# Sheet1.net
KiCad netlist of a schematic drawn in Altium Designer
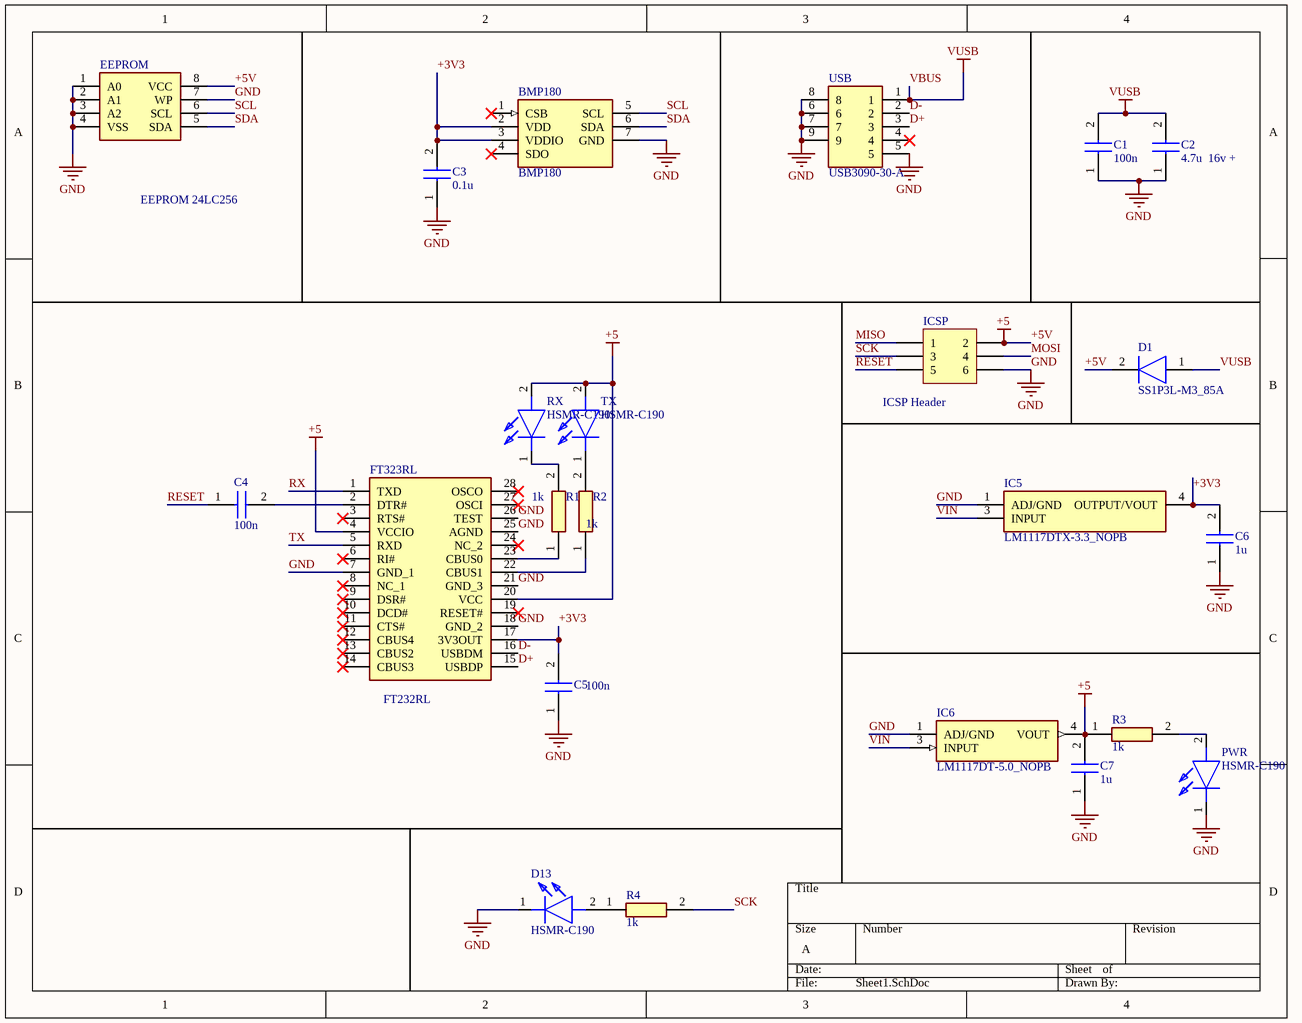
[diagram p0: Sheet1.SchDoc]

(export (version "E")
  (design (tool "Eeschema 10.0.6"))
  (components
    (comp (ref "BMP180")
      (value "BMP180")
      (footprint "SamacSys:BMP180")
      (description "Integrated Circuit")
      (fields (field (name "MOUSER PART NUMBER") "262-BMP180"))
      (libsource (lib "SamacSys") (part "BMP180"))
    )
    (comp (ref "C1")
      (value "100n")
      (footprint "SamacSys:CAPC1608X87N")
      (description "Capacitor")
      (fields (field (name "MANUFACTURER_PART_NUMBER") "C0603C569J5GACTU"))
      (libsource (lib "SamacSys") (part "C0603C569J5GACTU"))
    )
    (comp (ref "C2")
      (value "4.7u  16v +")
      (footprint "SamacSys:CAPC1608X87N")
      (description "Capacitor")
      (fields (field (name "MANUFACTURER_PART_NUMBER") "C0603C569J5GACTU"))
      (libsource (lib "SamacSys") (part "C0603C569J5GACTU"))
    )
    (comp (ref "C3")
      (value "0.1u")
      (footprint "SamacSys:CAPC1608X87N")
      (description "Capacitor")
      (fields (field (name "MANUFACTURER_PART_NUMBER") "C0603C569J5GACTU"))
      (libsource (lib "*") (part "C0603C569J5GACTU"))
    )
    (comp (ref "C4")
      (value "100n")
      (footprint "SamacSys:CAPC1608X87N")
      (description "Capacitor")
      (fields (field (name "MANUFACTURER_PART_NUMBER") "C0603C569J5GACTU"))
      (libsource (lib "*") (part "C0603C569J5GACTU"))
    )
    (comp (ref "C5")
      (value "100n")
      (footprint "SamacSys:CAPC1608X87N")
      (description "Capacitor")
      (fields (field (name "MANUFACTURER_PART_NUMBER") "C0603C569J5GACTU"))
      (libsource (lib "SamacSys") (part "C0603C569J5GACTU"))
    )
    (comp (ref "C6")
      (value "1u")
      (footprint "SamacSys:CAPC1608X87N")
      (description "Capacitor")
      (fields (field (name "MANUFACTURER_PART_NUMBER") "C0603C569J5GACTU"))
      (libsource (lib "SamacSys") (part "C0603C569J5GACTU"))
    )
    (comp (ref "C7")
      (value "1u")
      (footprint "SamacSys:CAPC1608X87N")
      (description "Capacitor")
      (fields (field (name "MANUFACTURER_PART_NUMBER") "C0603C569J5GACTU"))
      (libsource (lib "SamacSys") (part "C0603C569J5GACTU"))
    )
    (comp (ref "D1")
      (value "SS1P3L-M3_85A")
      (footprint "SamacSys:SMP")
      (description "Diode")
      (fields
        (field (name "MANUFACTURER_PART_NUMBER") "SS1P3L-M3/85A")
        (field (name "MOUSER PART NUMBER") "625-SS1P3L-M3/85A")
      )
      (libsource (lib "SamacSys") (part "SS1P3L-M3_85A"))
    )
    (comp (ref "D13")
      (value "HSMR-C190")
      (footprint "SamacSys:LEDC1608X80N")
      (description "LED")
      (fields (field (name "MOUSER PART NUMBER") "630-HSMR-C190"))
      (libsource (lib "SamacSys") (part "HSMR-C190"))
    )
    (comp (ref "EEPROM")
      (value "EEPROM 24LC256")
      (footprint "SamacSys:SOP65P490X110-8N")
      (description "Integrated Circuit")
      (fields
        (field (name "MANUFACTURER_PART_NUMBER") "24LC256-I/MS")
        (field (name "MOUSER PART NUMBER") "579-24LC256-I/MS")
      )
      (libsource (lib "*") (part "24LC256-I_MS"))
    )
    (comp (ref "FT323RL")
      (value "FT232RL")
      (footprint "SamacSys:SOP65P778X200-28N")
      (description "Integrated Circuit")
      (fields
        (field (name "MANUFACTURER_PART_NUMBER") "FT232RL-REEL")
        (field (name "MOUSER PART NUMBER") "895-FT232RL")
      )
      (libsource (lib "*") (part "FT232RL-REEL"))
    )
    (comp (ref "IC5")
      (value "LM1117DTX-3.3_NOPB")
      (footprint "SamacSys:LM1117DTX33NOPB")
      (description "Integrated Circuit")
      (fields
        (field (name "MANUFACTURER_PART_NUMBER") "LM1117DTX-3.3/NOPB")
        (field (name "MOUSER PART NUMBER") "926-LM1117DTX3.3NOPB")
      )
      (libsource (lib "SamacSys") (part "LM1117DTX-3.3_NOPB"))
    )
    (comp (ref "IC6")
      (value "LM1117DT-5.0_NOPB")
      (footprint "SamacSys:TO228P991X238-3N")
      (description "Integrated Circuit")
      (fields
        (field (name "MANUFACTURER_PART_NUMBER") "LM1117DT-5.0/NOPB")
        (field (name "MOUSER PART NUMBER") "926-LM1117DT50NOPB")
      )
      (libsource (lib "SamacSys") (part "LM1117DT-5.0_NOPB"))
    )
    (comp (ref "ICSP")
      (value "ICSP Header")
      (footprint "HDR2X3")
      (description "Header, 3-Pin, Dual row")
      (fields (field (name "PUBLISHER") "Altium Limited"))
      (libsource (lib "Miscellaneous Connectors") (part "Header 3X2"))
    )
    (comp (ref "PWR")
      (value "HSMR-C190")
      (footprint "SamacSys:LEDC1608X80N")
      (description "LED")
      (fields (field (name "MOUSER PART NUMBER") "630-HSMR-C190"))
      (libsource (lib "SamacSys") (part "HSMR-C190"))
    )
    (comp (ref "R1")
      (value "1k")
      (footprint "SamacSys:RESC2012X65N")
      (description "Resistor")
      (fields (field (name "MANUFACTURER_PART_NUMBER") "CPF0805B340RE1"))
      (libsource (lib "*") (part "CPF0805B340RE1"))
    )
    (comp (ref "R2")
      (value "1k")
      (footprint "SamacSys:RESC2012X65N")
      (description "Resistor")
      (fields (field (name "MANUFACTURER_PART_NUMBER") "CPF0805B340RE1"))
      (libsource (lib "*") (part "CPF0805B340RE1"))
    )
    (comp (ref "R3")
      (value "1k")
      (footprint "SamacSys:RESC2012X65N")
      (description "Resistor")
      (fields (field (name "MANUFACTURER_PART_NUMBER") "CPF0805B340RE1"))
      (libsource (lib "") (part "CPF0805B340RE1_1"))
    )
    (comp (ref "R4")
      (value "1k")
      (footprint "SamacSys:RESC2012X65N")
      (description "Resistor")
      (fields (field (name "MANUFACTURER_PART_NUMBER") "CPF0805B340RE1"))
      (libsource (lib "SamacSys") (part "CPF0805B340RE1"))
    )
    (comp (ref "RX")
      (value "HSMR-C190")
      (footprint "SamacSys:LEDC1608X80N")
      (description "LED")
      (fields (field (name "MOUSER PART NUMBER") "630-HSMR-C190"))
      (libsource (lib "SamacSys") (part "HSMR-C190"))
    )
    (comp (ref "TX")
      (value "HSMR-C190")
      (footprint "SamacSys:LEDC1608X80N")
      (description "LED")
      (fields (field (name "MOUSER PART NUMBER") "630-HSMR-C190"))
      (libsource (lib "SamacSys") (part "HSMR-C190"))
    )
    (comp (ref "USB")
      (value "USB3090-30-A")
      (footprint "SamacSys:USB309030A")
      (description "Connector")
      (libsource (lib "SamacSys") (part "USB3090-30-A"))
    )
  )
  (nets
    (net (code "1") (name "+5") (class "Default")
      (node (ref "C7") (pin "2") (pinfunction "2_2") (pintype "passive"))
      (node (ref "D1") (pin "2") (pinfunction "K_2") (pintype "passive"))
      (node (ref "EEPROM") (pin "8") (pinfunction "VCC_8") (pintype "passive"))
      (node (ref "FT323RL") (pin "20") (pinfunction "VCC_20") (pintype "passive"))
      (node (ref "FT323RL") (pin "4") (pinfunction "VCCIO_4") (pintype "passive"))
      (node (ref "IC6") (pin "4") (pinfunction "VOUT_4") (pintype "output"))
      (node (ref "ICSP") (pin "2") (pinfunction "2_2") (pintype "passive"))
      (node (ref "R3") (pin "1") (pinfunction "1_1") (pintype "passive"))
      (node (ref "RX") (pin "2") (pinfunction "A_2") (pintype "passive"))
      (node (ref "TX") (pin "2") (pinfunction "A_2") (pintype "passive"))
    )
    (net (code "2") (name "/+3V3") (class "Default")
      (node (ref "BMP180") (pin "2") (pinfunction "VDD_2") (pintype "power_in"))
      (node (ref "BMP180") (pin "3") (pinfunction "VDDIO_3") (pintype "power_in"))
      (node (ref "C3") (pin "2") (pinfunction "2_2") (pintype "passive"))
      (node (ref "C5") (pin "2") (pinfunction "2_2") (pintype "passive"))
      (node (ref "C6") (pin "2") (pinfunction "2_2") (pintype "passive"))
      (node (ref "FT323RL") (pin "17") (pinfunction "3V3OUT_17") (pintype "passive"))
      (node (ref "IC5") (pin "4") (pinfunction "OUTPUT/VOUT_4") (pintype "passive"))
    )
    (net (code "3") (name "/D+") (class "Default")
      (node (ref "FT323RL") (pin "15") (pinfunction "USBDP_15") (pintype "passive"))
      (node (ref "USB") (pin "3") (pinfunction "3_3") (pintype "passive"))
    )
    (net (code "4") (name "/D-") (class "Default")
      (node (ref "FT323RL") (pin "16") (pinfunction "USBDM_16") (pintype "passive"))
      (node (ref "USB") (pin "2") (pinfunction "2_2") (pintype "passive"))
    )
    (net (code "5") (name "/MISO") (class "Default")
      (node (ref "ICSP") (pin "1") (pinfunction "1_1") (pintype "passive"))
    )
    (net (code "6") (name "/MOSI") (class "Default")
      (node (ref "ICSP") (pin "4") (pinfunction "4_4") (pintype "passive"))
    )
    (net (code "7") (name "/RESET") (class "Default")
      (node (ref "C4") (pin "1") (pinfunction "1_1") (pintype "passive"))
      (node (ref "ICSP") (pin "5") (pinfunction "5_5") (pintype "passive"))
    )
    (net (code "8") (name "/RX") (class "Default")
      (node (ref "FT323RL") (pin "1") (pinfunction "TXD_1") (pintype "passive"))
    )
    (net (code "9") (name "/SCK") (class "Default")
      (node (ref "ICSP") (pin "3") (pinfunction "3_3") (pintype "passive"))
      (node (ref "R4") (pin "2") (pinfunction "2_2") (pintype "passive"))
    )
    (net (code "10") (name "/SCL") (class "Default")
      (node (ref "BMP180") (pin "5") (pinfunction "SCL_5") (pintype "passive"))
      (node (ref "EEPROM") (pin "6") (pinfunction "SCL_6") (pintype "passive"))
    )
    (net (code "11") (name "/SDA") (class "Default")
      (node (ref "BMP180") (pin "6") (pinfunction "SDA_6") (pintype "passive"))
      (node (ref "EEPROM") (pin "5") (pinfunction "SDA_5") (pintype "passive"))
    )
    (net (code "12") (name "/TX") (class "Default")
      (node (ref "FT323RL") (pin "5") (pinfunction "RXD_5") (pintype "passive"))
    )
    (net (code "13") (name "/VIN") (class "Default")
      (node (ref "IC5") (pin "3") (pinfunction "INPUT_3") (pintype "passive"))
      (node (ref "IC6") (pin "3") (pinfunction "INPUT_3") (pintype "input"))
    )
    (net (code "14") (name "GND") (class "Default")
      (node (ref "BMP180") (pin "7") (pinfunction "GND_7") (pintype "power_in"))
      (node (ref "C1") (pin "1") (pinfunction "1_1") (pintype "passive"))
      (node (ref "C2") (pin "1") (pinfunction "1_1") (pintype "passive"))
      (node (ref "C3") (pin "1") (pinfunction "1_1") (pintype "passive"))
      (node (ref "C5") (pin "1") (pinfunction "1_1") (pintype "passive"))
      (node (ref "C6") (pin "1") (pinfunction "1_1") (pintype "passive"))
      (node (ref "C7") (pin "1") (pinfunction "1_1") (pintype "passive"))
      (node (ref "D13") (pin "1") (pinfunction "K_1") (pintype "passive"))
      (node (ref "EEPROM") (pin "1") (pinfunction "A0_1") (pintype "passive"))
      (node (ref "EEPROM") (pin "2") (pinfunction "A1_2") (pintype "passive"))
      (node (ref "EEPROM") (pin "3") (pinfunction "A2_3") (pintype "passive"))
      (node (ref "EEPROM") (pin "4") (pinfunction "VSS_4") (pintype "passive"))
      (node (ref "EEPROM") (pin "7") (pinfunction "WP_7") (pintype "passive"))
      (node (ref "FT323RL") (pin "18") (pinfunction "GND_2_18") (pintype "passive"))
      (node (ref "FT323RL") (pin "21") (pinfunction "GND_3_21") (pintype "passive"))
      (node (ref "FT323RL") (pin "25") (pinfunction "AGND_25") (pintype "passive"))
      (node (ref "FT323RL") (pin "26") (pinfunction "TEST_26") (pintype "passive"))
      (node (ref "FT323RL") (pin "7") (pinfunction "GND_1_7") (pintype "passive"))
      (node (ref "IC5") (pin "1") (pinfunction "ADJ/GND_1") (pintype "passive"))
      (node (ref "IC6") (pin "1") (pinfunction "ADJ/GND_1") (pintype "power_in"))
      (node (ref "ICSP") (pin "6") (pinfunction "6_6") (pintype "passive"))
      (node (ref "PWR") (pin "1") (pinfunction "K_1") (pintype "passive"))
      (node (ref "USB") (pin "5") (pinfunction "5_5") (pintype "passive"))
      (node (ref "USB") (pin "6") (pinfunction "6_6") (pintype "passive"))
      (node (ref "USB") (pin "7") (pinfunction "7_7") (pintype "passive"))
      (node (ref "USB") (pin "8") (pinfunction "8_8") (pintype "passive"))
      (node (ref "USB") (pin "9") (pinfunction "9_9") (pintype "passive"))
    )
    (net (code "15") (name "Net-(D13-A)") (class "Default")
      (node (ref "D13") (pin "2") (pinfunction "A_2") (pintype "passive"))
      (node (ref "R4") (pin "1") (pinfunction "1_1") (pintype "passive"))
    )
    (net (code "16") (name "Net-(FT323RL-CBUS0)") (class "Default")
      (node (ref "FT323RL") (pin "23") (pinfunction "CBUS0_23") (pintype "passive"))
      (node (ref "R1") (pin "1") (pinfunction "1_1") (pintype "passive"))
    )
    (net (code "17") (name "Net-(FT323RL-CBUS1)") (class "Default")
      (node (ref "FT323RL") (pin "22") (pinfunction "CBUS1_22") (pintype "passive"))
      (node (ref "R2") (pin "1") (pinfunction "1_1") (pintype "passive"))
    )
    (net (code "18") (name "Net-(FT323RL-DTR#)") (class "Default")
      (node (ref "C4") (pin "2") (pinfunction "2_2") (pintype "passive"))
      (node (ref "FT323RL") (pin "2") (pinfunction "DTR#_2") (pintype "passive"))
    )
    (net (code "19") (name "Net-(PWR-A)") (class "Default")
      (node (ref "PWR") (pin "2") (pinfunction "A_2") (pintype "passive"))
      (node (ref "R3") (pin "2") (pinfunction "2_2") (pintype "passive"))
    )
    (net (code "20") (name "Net-(RX-K)") (class "Default")
      (node (ref "R1") (pin "2") (pinfunction "2_2") (pintype "passive"))
      (node (ref "RX") (pin "1") (pinfunction "K_1") (pintype "passive"))
    )
    (net (code "21") (name "Net-(TX-K)") (class "Default")
      (node (ref "R2") (pin "2") (pinfunction "2_2") (pintype "passive"))
      (node (ref "TX") (pin "1") (pinfunction "K_1") (pintype "passive"))
    )
    (net (code "22") (name "VUSB") (class "Default")
      (node (ref "C1") (pin "2") (pinfunction "2_2") (pintype "passive"))
      (node (ref "C2") (pin "2") (pinfunction "2_2") (pintype "passive"))
      (node (ref "D1") (pin "1") (pinfunction "A_1") (pintype "passive"))
      (node (ref "USB") (pin "1") (pinfunction "1_1") (pintype "passive"))
    )
    (net (code "23") (name "unconnected-(BMP180-CSB-Pad1)") (class "Default")
      (node (ref "BMP180") (pin "1") (pinfunction "CSB_1") (pintype "input+no_connect"))
    )
    (net (code "24") (name "unconnected-(BMP180-SDO-Pad4)") (class "Default")
      (node (ref "BMP180") (pin "4") (pinfunction "SDO_4") (pintype "passive+no_connect"))
    )
    (net (code "25") (name "unconnected-(FT323RL-CBUS2-Pad13)") (class "Default")
      (node (ref "FT323RL") (pin "13") (pinfunction "CBUS2_13") (pintype "passive+no_connect"))
    )
    (net (code "26") (name "unconnected-(FT323RL-CBUS3-Pad14)") (class "Default")
      (node (ref "FT323RL") (pin "14") (pinfunction "CBUS3_14") (pintype "passive+no_connect"))
    )
    (net (code "27") (name "unconnected-(FT323RL-CBUS4-Pad12)") (class "Default")
      (node (ref "FT323RL") (pin "12") (pinfunction "CBUS4_12") (pintype "passive+no_connect"))
    )
    (net (code "28") (name "unconnected-(FT323RL-CTS#-Pad11)") (class "Default")
      (node (ref "FT323RL") (pin "11") (pinfunction "CTS#_11") (pintype "passive+no_connect"))
    )
    (net (code "29") (name "unconnected-(FT323RL-DCD#-Pad10)") (class "Default")
      (node (ref "FT323RL") (pin "10") (pinfunction "DCD#_10") (pintype "passive+no_connect"))
    )
    (net (code "30") (name "unconnected-(FT323RL-DSR#-Pad9)") (class "Default")
      (node (ref "FT323RL") (pin "9") (pinfunction "DSR#_9") (pintype "passive+no_connect"))
    )
    (net (code "31") (name "unconnected-(FT323RL-NC_1-Pad8)") (class "Default")
      (node (ref "FT323RL") (pin "8") (pinfunction "NC_1_8") (pintype "passive+no_connect"))
    )
    (net (code "32") (name "unconnected-(FT323RL-NC_2-Pad24)") (class "Default")
      (node (ref "FT323RL") (pin "24") (pinfunction "NC_2_24") (pintype "passive+no_connect"))
    )
    (net (code "33") (name "unconnected-(FT323RL-OSCI-Pad27)") (class "Default")
      (node (ref "FT323RL") (pin "27") (pinfunction "OSCI_27") (pintype "passive+no_connect"))
    )
    (net (code "34") (name "unconnected-(FT323RL-OSCO-Pad28)") (class "Default")
      (node (ref "FT323RL") (pin "28") (pinfunction "OSCO_28") (pintype "passive+no_connect"))
    )
    (net (code "35") (name "unconnected-(FT323RL-RESET#-Pad19)") (class "Default")
      (node (ref "FT323RL") (pin "19") (pinfunction "RESET#_19") (pintype "passive+no_connect"))
    )
    (net (code "36") (name "unconnected-(FT323RL-RI#-Pad6)") (class "Default")
      (node (ref "FT323RL") (pin "6") (pinfunction "RI#_6") (pintype "passive+no_connect"))
    )
    (net (code "37") (name "unconnected-(FT323RL-RTS#-Pad3)") (class "Default")
      (node (ref "FT323RL") (pin "3") (pinfunction "RTS#_3") (pintype "passive+no_connect"))
    )
    (net (code "38") (name "unconnected-(USB-Pad4)") (class "Default")
      (node (ref "USB") (pin "4") (pinfunction "4_4") (pintype "passive+no_connect"))
    )
  )
)
